# SCH_My-Second-Take_2024-06-22.net
KiCad netlist of a schematic drawn in EasyEDA
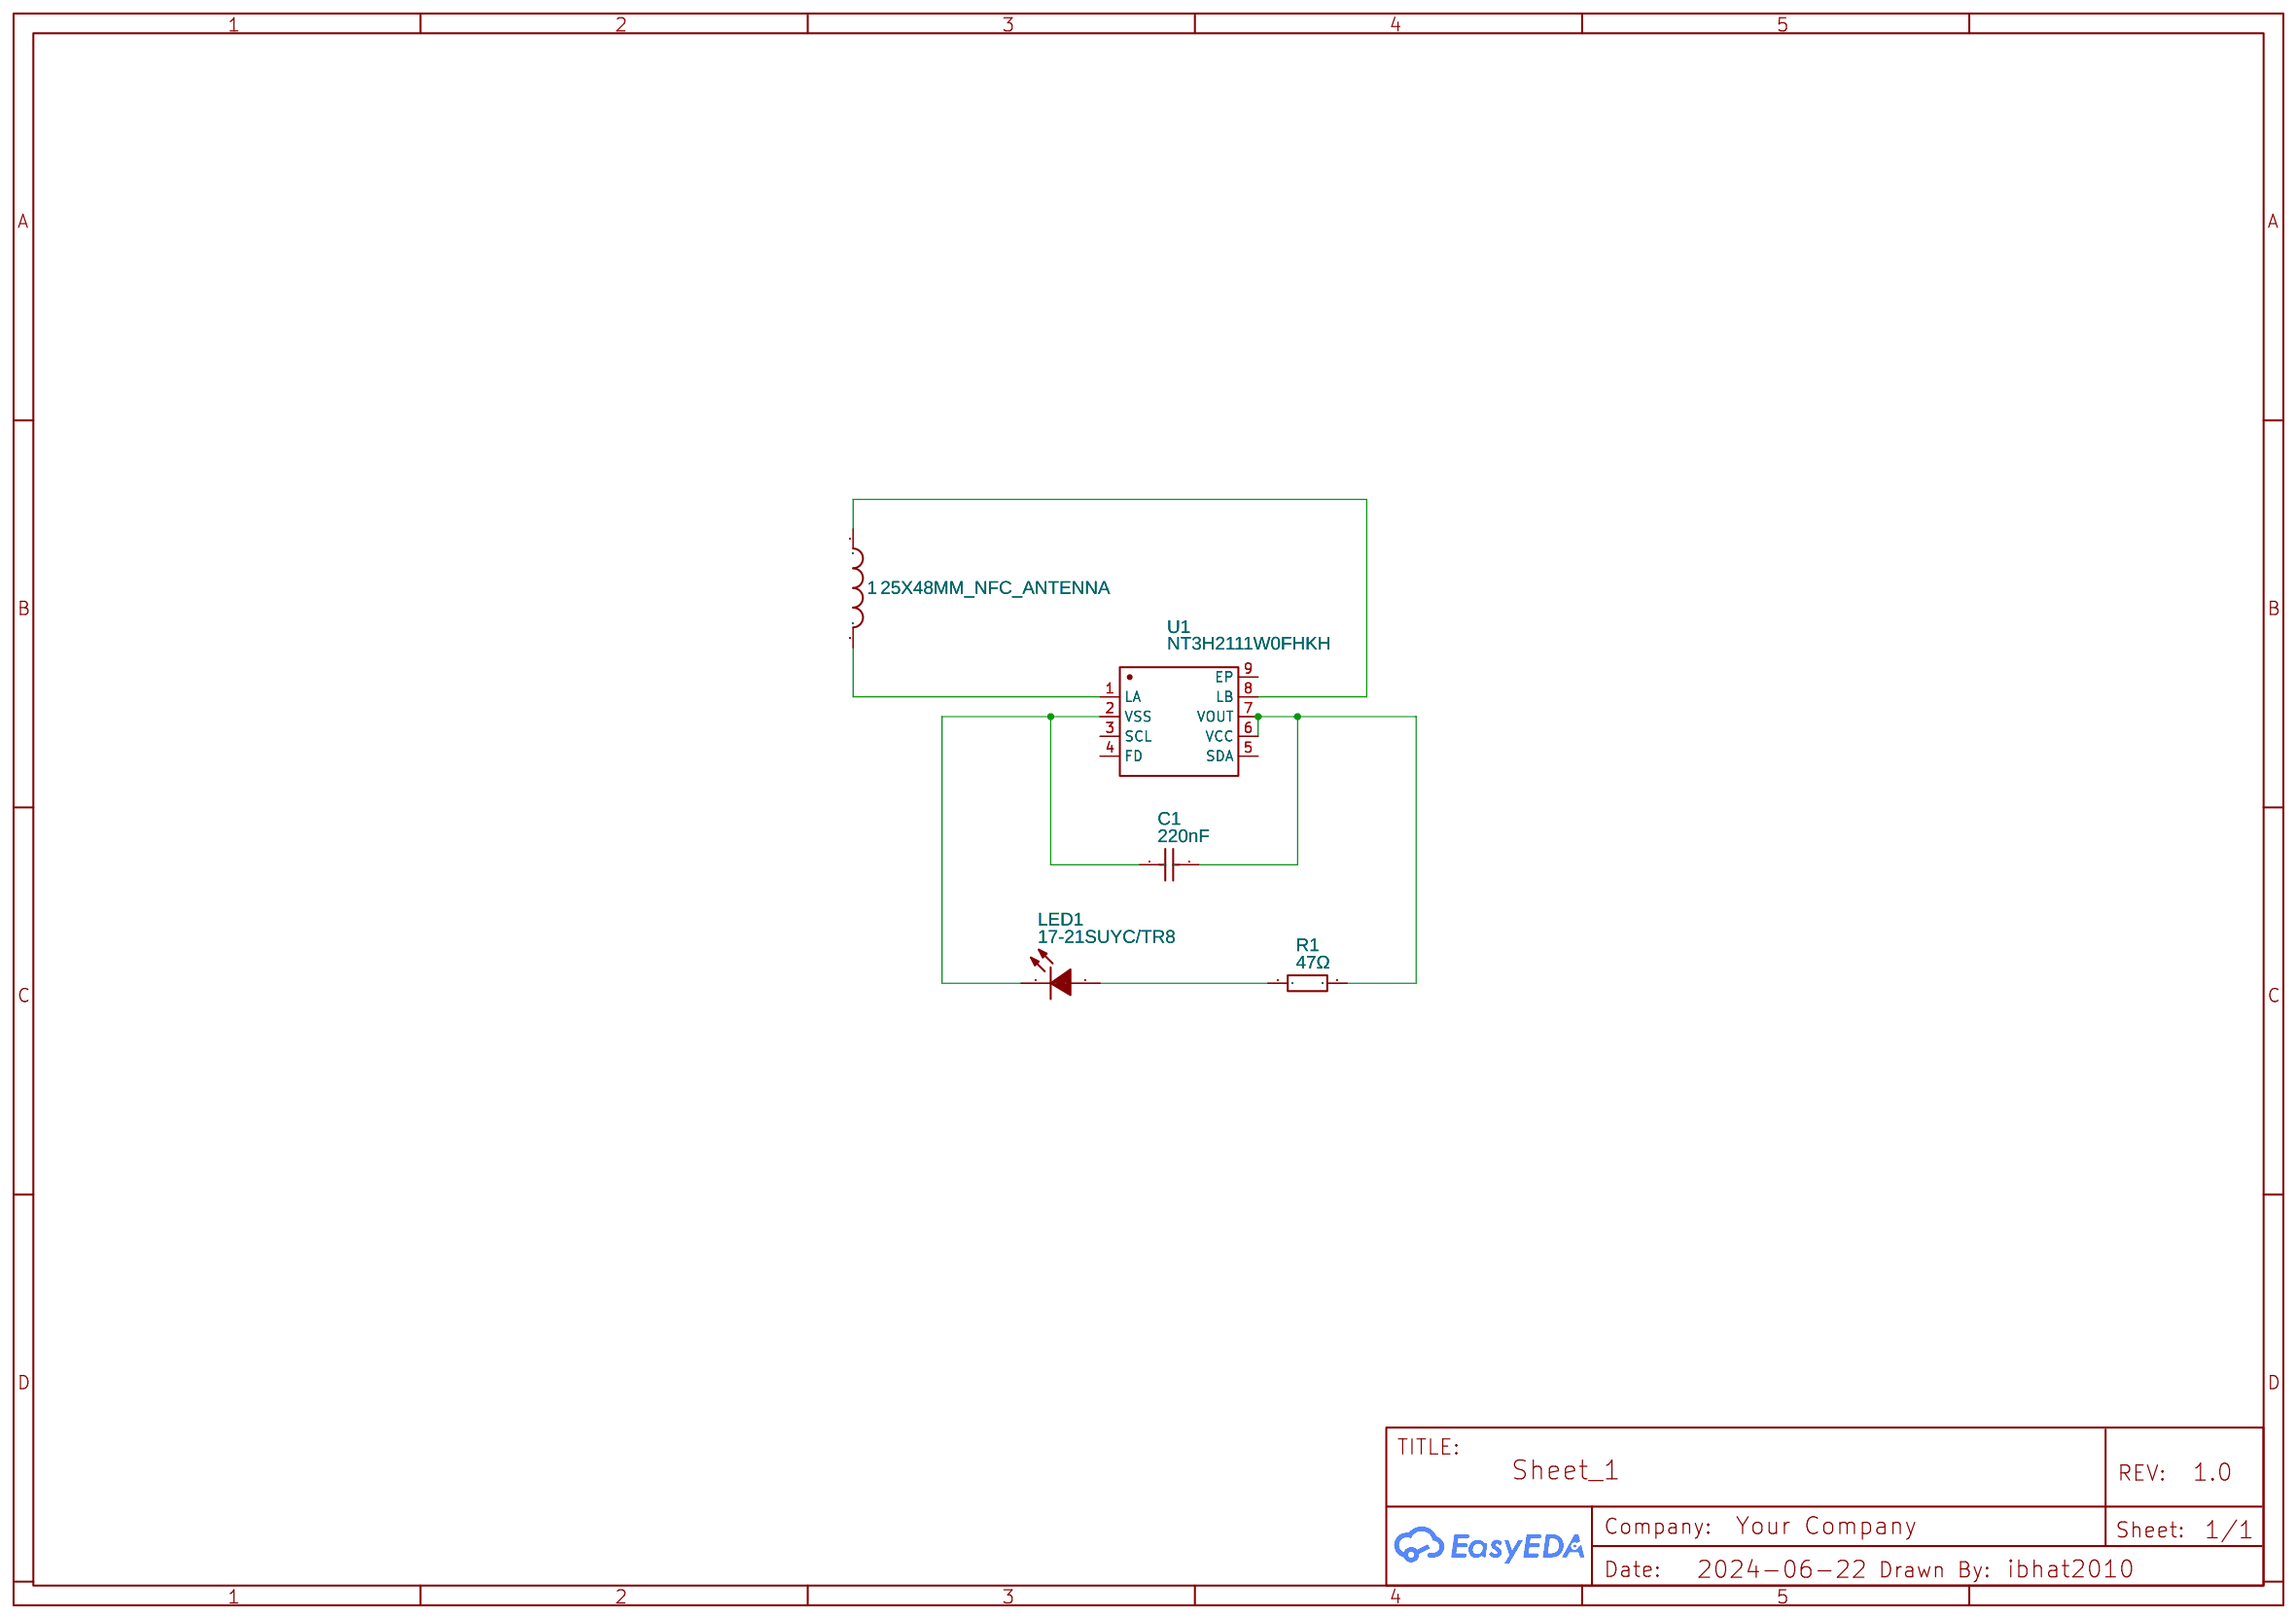
[diagram p0: schematic sheet]

(export (version "E")
  (design (tool "Eeschema 10.0.6"))
  (components
    (comp (ref "1") (value "25X48MM_NFC_ANTENNA") (libsource (lib "") (part "25X48MM_NFC_ANTENNA")))
    (comp (ref "C1")
      (value "220nF")
      (fields
        (field (name "Manufacturer Part") "CL10B224KA8NNNC")
        (field (name "Manufacturer") "SAMSUNG(三星)")
      )
      (libsource (lib "") (part "CL10B224KA8NNNC"))
    )
    (comp (ref "LED1")
      (value "17-21SUYC/TR8")
      (fields (field (name "Manufacturer Part") "KT-0805黄灯") (field (name "Manufacturer") "KENTO"))
      (libsource (lib "") (part "17-21SUYC/TR8"))
    )
    (comp (ref "R1")
      (value "47Ω")
      (fields
        (field (name "Manufacturer Part") "0603WAF470JT5E")
        (field (name "Manufacturer") "UNI-ROYAL(厚声)")
      )
      (libsource (lib "") (part "0603WAF470JT5E"))
    )
    (comp (ref "U1")
      (value "NT3H2111W0FHKH")
      (fields (field (name "Manufacturer") "NXP(恩智浦)"))
      (libsource (lib "") (part "NT3H2111W0FHKH"))
    )
  )
  (nets
    (net (code "1") (name "Net-(LED1-+)") (class "Default")
      (node (ref "LED1") (pin "1") (pinfunction "+_1") (pintype "unspecified"))
      (node (ref "R1") (pin "1") (pinfunction "1_1") (pintype "input"))
    )
    (net (code "2") (name "Net-(LED1--)") (class "Default")
      (node (ref "C1") (pin "1") (pinfunction "1_1") (pintype "input"))
      (node (ref "LED1") (pin "2") (pinfunction "-_2") (pintype "unspecified"))
      (node (ref "U1") (pin "2") (pinfunction "VSS_2") (pintype "unspecified"))
    )
    (net (code "3") (name "Net-(U1-LA)") (class "Default")
      (node (ref "1") (pin "P$2") (pinfunction "P$2_P$2") (pintype "bidirectional"))
      (node (ref "U1") (pin "1") (pinfunction "LA_1") (pintype "unspecified"))
    )
    (net (code "4") (name "Net-(U1-LB)") (class "Default")
      (node (ref "1") (pin "P$1") (pinfunction "P$1_P$1") (pintype "bidirectional"))
      (node (ref "U1") (pin "8") (pinfunction "LB_8") (pintype "unspecified"))
    )
    (net (code "5") (name "Net-(U1-VCC)") (class "Default")
      (node (ref "C1") (pin "2") (pinfunction "2_2") (pintype "input"))
      (node (ref "R1") (pin "2") (pinfunction "2_2") (pintype "input"))
      (node (ref "U1") (pin "6") (pinfunction "VCC_6") (pintype "unspecified"))
      (node (ref "U1") (pin "7") (pinfunction "VOUT_7") (pintype "unspecified"))
    )
    (net (code "6") (name "unconnected-(U1-EP-Pad9)") (class "Default")
      (node (ref "U1") (pin "9") (pinfunction "EP_9") (pintype "unspecified"))
    )
    (net (code "7") (name "unconnected-(U1-FD-Pad4)") (class "Default")
      (node (ref "U1") (pin "4") (pinfunction "FD_4") (pintype "unspecified"))
    )
    (net (code "8") (name "unconnected-(U1-SCL-Pad3)") (class "Default")
      (node (ref "U1") (pin "3") (pinfunction "SCL_3") (pintype "unspecified"))
    )
    (net (code "9") (name "unconnected-(U1-SDA-Pad5)") (class "Default")
      (node (ref "U1") (pin "5") (pinfunction "SDA_5") (pintype "unspecified"))
    )
  )
)
